# Main.net
KiCad netlist of a schematic drawn in Altium Designer
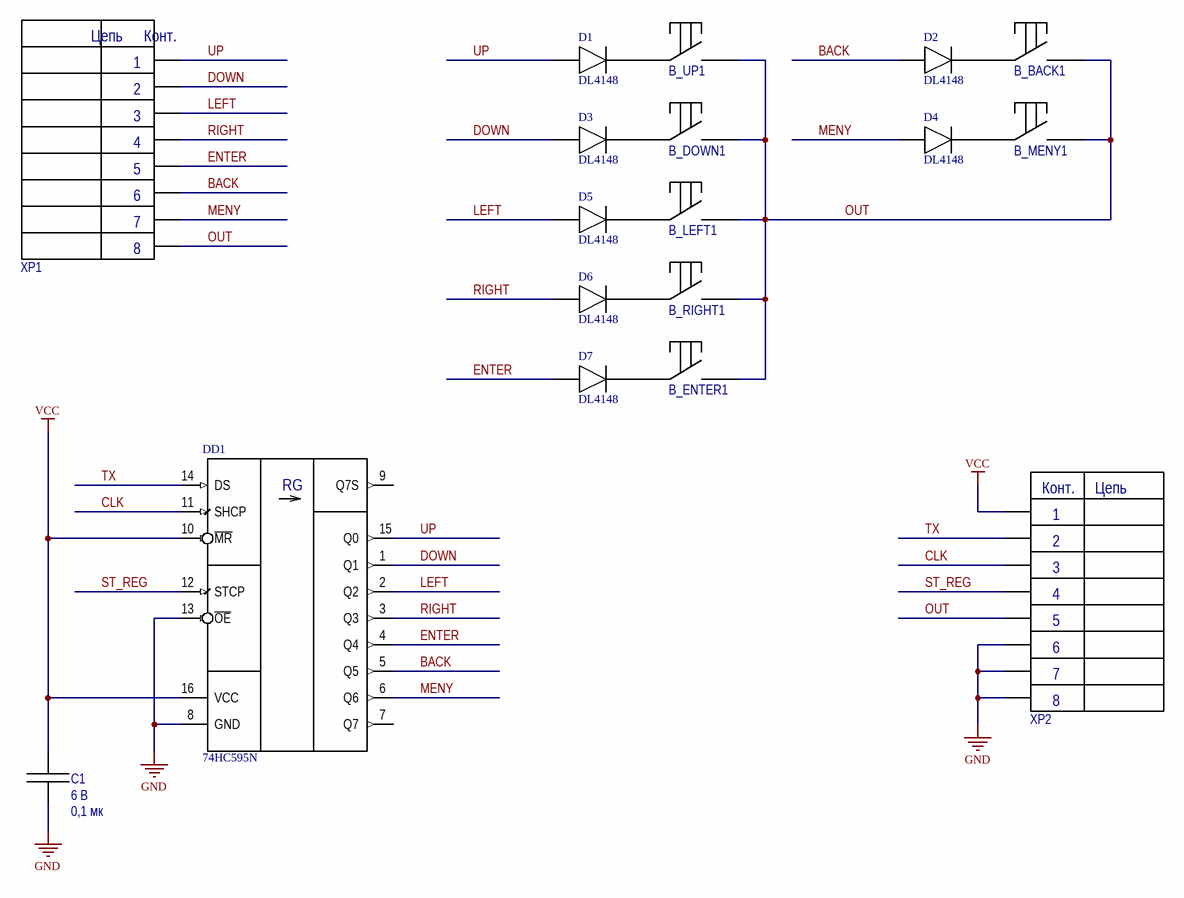
[diagram p0: Main.SchDoc]

(export (version "E")
  (design (tool "Eeschema 10.0.6"))
  (components
    (comp (ref "B_BACK1")
      (value "Tact_switch")
      (footprint "Tact_switch_6x6x5")
      (description "SMD pushbutton")
      (fields (field (name "MANUFACTURER") "NONAME"))
      (libsource (lib "connectors+switches") (part "Tact_switch"))
    )
    (comp (ref "B_DOWN1")
      (value "Tact_switch")
      (footprint "Tact_switch_6x6x5")
      (description "SMD pushbutton")
      (fields (field (name "MANUFACTURER") "NONAME"))
      (libsource (lib "connectors+switches") (part "Tact_switch"))
    )
    (comp (ref "B_ENTER1")
      (value "Tact_switch")
      (footprint "Tact_switch_6x6x5")
      (description "SMD pushbutton")
      (fields (field (name "MANUFACTURER") "NONAME"))
      (libsource (lib "connectors+switches") (part "Tact_switch"))
    )
    (comp (ref "B_LEFT1")
      (value "Tact_switch")
      (footprint "Tact_switch_6x6x5")
      (description "SMD pushbutton")
      (fields (field (name "MANUFACTURER") "NONAME"))
      (libsource (lib "connectors+switches") (part "Tact_switch"))
    )
    (comp (ref "B_MENY1")
      (value "Tact_switch")
      (footprint "Tact_switch_6x6x5")
      (description "SMD pushbutton")
      (fields (field (name "MANUFACTURER") "NONAME"))
      (libsource (lib "connectors+switches") (part "Tact_switch"))
    )
    (comp (ref "B_RIGHT1")
      (value "Tact_switch")
      (footprint "Tact_switch_6x6x5")
      (description "SMD pushbutton")
      (fields (field (name "MANUFACTURER") "NONAME"))
      (libsource (lib "connectors+switches") (part "Tact_switch"))
    )
    (comp (ref "B_UP1")
      (value "Tact_switch")
      (footprint "Tact_switch_6x6x5")
      (description "SMD pushbutton")
      (fields (field (name "MANUFACTURER") "NONAME"))
      (libsource (lib "connectors+switches") (part "Tact_switch"))
    )
    (comp (ref "C1")
      (value "0,1 мк")
      (footprint "C_1206_Manual_mount")
      (description "SMD Capacitor 1206")
      (fields
        (field (name "TOLERANCE") "/Укажите допуск в процентах/")
        (field (name "MANUFACTURER") "/Укажите компанию-производителя/")
        (field (name "RATED VOLTAGE") "6 В")
      )
      (libsource (lib "passive") (part "Capacitor 1206"))
    )
    (comp (ref "D1") (value "DL4148") (footprint "DL-35") (libsource (lib "vadimatorik_lib") (part "DL4148")))
    (comp (ref "D2") (value "DL4148") (footprint "DL-35") (libsource (lib "vadimatorik_lib") (part "DL4148")))
    (comp (ref "D3") (value "DL4148") (footprint "DL-35") (libsource (lib "vadimatorik_lib") (part "DL4148")))
    (comp (ref "D4") (value "DL4148") (footprint "DL-35") (libsource (lib "vadimatorik_lib") (part "DL4148")))
    (comp (ref "D5") (value "DL4148") (footprint "DL-35") (libsource (lib "vadimatorik_lib") (part "DL4148")))
    (comp (ref "D6") (value "DL4148") (footprint "DL-35") (libsource (lib "vadimatorik_lib") (part "DL4148")))
    (comp (ref "D7") (value "DL4148") (footprint "DL-35") (libsource (lib "vadimatorik_lib") (part "DL4148")))
    (comp (ref "DD1") (value "74HC595N") (footprint "SO16") (libsource (lib "my_lib") (part "74HC595N")))
    (comp (ref "XP1")
      (value "PLD-8")
      (footprint "PLD-8")
      (description "PLD connector")
      (fields (field (name "MANUFACTURER") "NONAME"))
      (libsource (lib "my_lib") (part "PLD-8"))
    )
    (comp (ref "XP2")
      (value "PLD-8")
      (footprint "PLD-8")
      (description "PLD connector")
      (fields (field (name "MANUFACTURER") "NONAME"))
      (libsource (lib "my_lib") (part "PLD-8"))
    )
  )
  (nets
    (net (code "1") (name "/BACK") (class "Default")
      (node (ref "D2") (pin "A") (pinfunction "A_A") (pintype "passive"))
      (node (ref "DD1") (pin "5") (pinfunction "Q5_5") (pintype "output"))
      (node (ref "XP1") (pin "6") (pinfunction "6_6") (pintype "passive"))
    )
    (net (code "2") (name "/CLK") (class "Default")
      (node (ref "DD1") (pin "11") (pinfunction "SHCP_11") (pintype "input"))
      (node (ref "XP2") (pin "3") (pinfunction "3_3") (pintype "passive"))
    )
    (net (code "3") (name "/DOWN") (class "Default")
      (node (ref "D3") (pin "A") (pinfunction "A_A") (pintype "passive"))
      (node (ref "DD1") (pin "1") (pinfunction "Q1_1") (pintype "output"))
      (node (ref "XP1") (pin "2") (pinfunction "2_2") (pintype "passive"))
    )
    (net (code "4") (name "/ENTER") (class "Default")
      (node (ref "D7") (pin "A") (pinfunction "A_A") (pintype "passive"))
      (node (ref "DD1") (pin "4") (pinfunction "Q4_4") (pintype "output"))
      (node (ref "XP1") (pin "5") (pinfunction "5_5") (pintype "passive"))
    )
    (net (code "5") (name "/LEFT") (class "Default")
      (node (ref "D5") (pin "A") (pinfunction "A_A") (pintype "passive"))
      (node (ref "DD1") (pin "2") (pinfunction "Q2_2") (pintype "output"))
      (node (ref "XP1") (pin "3") (pinfunction "3_3") (pintype "passive"))
    )
    (net (code "6") (name "/MENY") (class "Default")
      (node (ref "D4") (pin "A") (pinfunction "A_A") (pintype "passive"))
      (node (ref "DD1") (pin "6") (pinfunction "Q6_6") (pintype "output"))
      (node (ref "XP1") (pin "7") (pinfunction "7_7") (pintype "passive"))
    )
    (net (code "7") (name "/OUT") (class "Default")
      (node (ref "B_BACK1") (pin "2") (pinfunction "2_2") (pintype "passive"))
      (node (ref "B_DOWN1") (pin "2") (pinfunction "2_2") (pintype "passive"))
      (node (ref "B_ENTER1") (pin "2") (pinfunction "2_2") (pintype "passive"))
      (node (ref "B_LEFT1") (pin "2") (pinfunction "2_2") (pintype "passive"))
      (node (ref "B_MENY1") (pin "2") (pinfunction "2_2") (pintype "passive"))
      (node (ref "B_RIGHT1") (pin "2") (pinfunction "2_2") (pintype "passive"))
      (node (ref "B_UP1") (pin "2") (pinfunction "2_2") (pintype "passive"))
      (node (ref "XP1") (pin "8") (pinfunction "8_8") (pintype "passive"))
      (node (ref "XP2") (pin "5") (pinfunction "5_5") (pintype "passive"))
    )
    (net (code "8") (name "/RIGHT") (class "Default")
      (node (ref "D6") (pin "A") (pinfunction "A_A") (pintype "passive"))
      (node (ref "DD1") (pin "3") (pinfunction "Q3_3") (pintype "output"))
      (node (ref "XP1") (pin "4") (pinfunction "4_4") (pintype "passive"))
    )
    (net (code "9") (name "/ST_REG") (class "Default")
      (node (ref "DD1") (pin "12") (pinfunction "STCP_12") (pintype "input"))
      (node (ref "XP2") (pin "4") (pinfunction "4_4") (pintype "passive"))
    )
    (net (code "10") (name "/TX") (class "Default")
      (node (ref "DD1") (pin "14") (pinfunction "DS_14") (pintype "input"))
      (node (ref "XP2") (pin "2") (pinfunction "2_2") (pintype "passive"))
    )
    (net (code "11") (name "/UP") (class "Default")
      (node (ref "D1") (pin "A") (pinfunction "A_A") (pintype "passive"))
      (node (ref "DD1") (pin "15") (pinfunction "Q0_15") (pintype "output"))
      (node (ref "XP1") (pin "1") (pinfunction "1_1") (pintype "passive"))
    )
    (net (code "12") (name "GND") (class "Default")
      (node (ref "C1") (pin "2") (pinfunction "2_2") (pintype "passive"))
      (node (ref "DD1") (pin "13") (pinfunction "~{OE}_13") (pintype "input"))
      (node (ref "DD1") (pin "8") (pinfunction "GND_8") (pintype "power_in"))
      (node (ref "XP2") (pin "6") (pinfunction "6_6") (pintype "passive"))
      (node (ref "XP2") (pin "7") (pinfunction "7_7") (pintype "passive"))
      (node (ref "XP2") (pin "8") (pinfunction "8_8") (pintype "passive"))
    )
    (net (code "13") (name "Net-(B_BACK1-Pad1)") (class "Default")
      (node (ref "B_BACK1") (pin "1") (pinfunction "1_1") (pintype "passive"))
      (node (ref "D2") (pin "C") (pinfunction "C_C") (pintype "passive"))
    )
    (net (code "14") (name "Net-(B_DOWN1-Pad1)") (class "Default")
      (node (ref "B_DOWN1") (pin "1") (pinfunction "1_1") (pintype "passive"))
      (node (ref "D3") (pin "C") (pinfunction "C_C") (pintype "passive"))
    )
    (net (code "15") (name "Net-(B_ENTER1-Pad1)") (class "Default")
      (node (ref "B_ENTER1") (pin "1") (pinfunction "1_1") (pintype "passive"))
      (node (ref "D7") (pin "C") (pinfunction "C_C") (pintype "passive"))
    )
    (net (code "16") (name "Net-(B_LEFT1-Pad1)") (class "Default")
      (node (ref "B_LEFT1") (pin "1") (pinfunction "1_1") (pintype "passive"))
      (node (ref "D5") (pin "C") (pinfunction "C_C") (pintype "passive"))
    )
    (net (code "17") (name "Net-(B_MENY1-Pad1)") (class "Default")
      (node (ref "B_MENY1") (pin "1") (pinfunction "1_1") (pintype "passive"))
      (node (ref "D4") (pin "C") (pinfunction "C_C") (pintype "passive"))
    )
    (net (code "18") (name "Net-(B_RIGHT1-Pad1)") (class "Default")
      (node (ref "B_RIGHT1") (pin "1") (pinfunction "1_1") (pintype "passive"))
      (node (ref "D6") (pin "C") (pinfunction "C_C") (pintype "passive"))
    )
    (net (code "19") (name "Net-(B_UP1-Pad1)") (class "Default")
      (node (ref "B_UP1") (pin "1") (pinfunction "1_1") (pintype "passive"))
      (node (ref "D1") (pin "C") (pinfunction "C_C") (pintype "passive"))
    )
    (net (code "20") (name "VCC") (class "Default")
      (node (ref "C1") (pin "1") (pinfunction "1_1") (pintype "passive"))
      (node (ref "DD1") (pin "10") (pinfunction "~{MR}_10") (pintype "input"))
      (node (ref "DD1") (pin "16") (pinfunction "VCC_16") (pintype "power_in"))
      (node (ref "XP2") (pin "1") (pinfunction "1_1") (pintype "passive"))
    )
    (net (code "21") (name "unconnected-(DD1-Q7-Pad7)") (class "Default")
      (node (ref "DD1") (pin "7") (pinfunction "Q7_7") (pintype "output"))
    )
    (net (code "22") (name "unconnected-(DD1-Q7S-Pad9)") (class "Default")
      (node (ref "DD1") (pin "9") (pinfunction "Q7S_9") (pintype "output"))
    )
  )
)
